# RedFly-Shield_v14.net
KiCad netlist of a schematic drawn in EAGLE
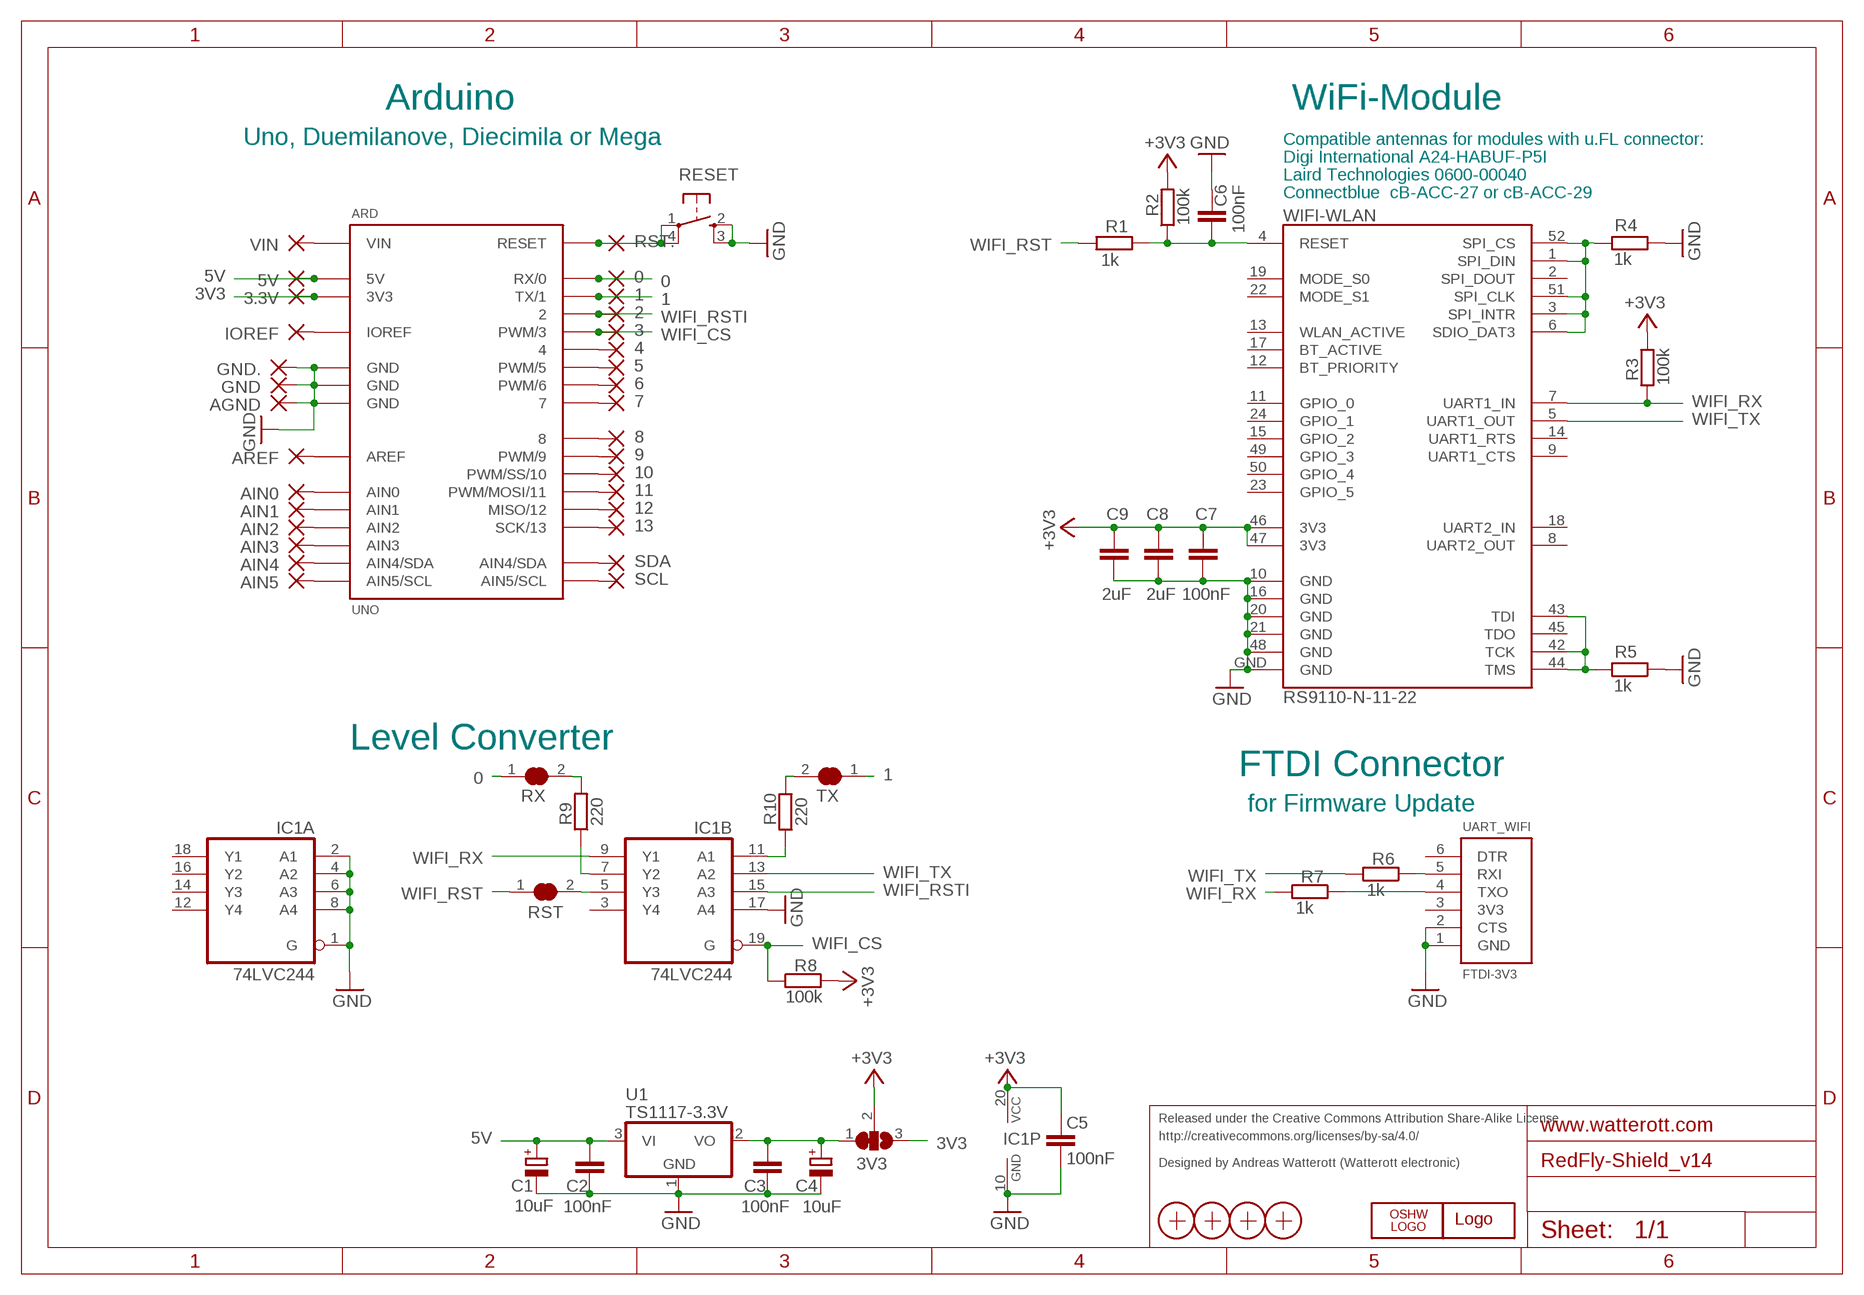
[diagram p0: schematic, sheet 1]

(export (version "E")
  (design (tool "Eeschema 10.0.6"))
  (components
    (comp (ref "0")
      (value "WIREPAD1,6/0,8")
      (footprint "eagle-import:1,6_0,8")
      (libsource (lib "eagle-import") (part "WIREPAD1,6/0,8"))
    )
    (comp (ref "1")
      (value "WIREPAD1,6/0,8")
      (footprint "eagle-import:1,6_0,8")
      (libsource (lib "eagle-import") (part "WIREPAD1,6/0,8"))
    )
    (comp (ref "2")
      (value "WIREPAD1,6/0,8")
      (footprint "eagle-import:1,6_0,8")
      (libsource (lib "eagle-import") (part "WIREPAD1,6/0,8"))
    )
    (comp (ref "3")
      (value "WIREPAD1,6/0,8")
      (footprint "eagle-import:1,6_0,8")
      (libsource (lib "eagle-import") (part "WIREPAD1,6/0,8"))
    )
    (comp (ref "3.3V")
      (value "WIREPAD1,6/0,8")
      (footprint "eagle-import:1,6_0,8")
      (libsource (lib "eagle-import") (part "WIREPAD1,6/0,8"))
    )
    (comp (ref "3V3")
      (value "SJ2W")
      (footprint "eagle-import:SJ_2")
      (libsource (lib "eagle-import") (part "SJ2W"))
    )
    (comp (ref "4")
      (value "WIREPAD1,6/0,8")
      (footprint "eagle-import:1,6_0,8")
      (libsource (lib "eagle-import") (part "WIREPAD1,6/0,8"))
    )
    (comp (ref "5")
      (value "WIREPAD1,6/0,8")
      (footprint "eagle-import:1,6_0,8")
      (libsource (lib "eagle-import") (part "WIREPAD1,6/0,8"))
    )
    (comp (ref "5V")
      (value "WIREPAD1,6/0,8")
      (footprint "eagle-import:1,6_0,8")
      (libsource (lib "eagle-import") (part "WIREPAD1,6/0,8"))
    )
    (comp (ref "6")
      (value "WIREPAD1,6/0,8")
      (footprint "eagle-import:1,6_0,8")
      (libsource (lib "eagle-import") (part "WIREPAD1,6/0,8"))
    )
    (comp (ref "7")
      (value "WIREPAD1,6/0,8")
      (footprint "eagle-import:1,6_0,8")
      (libsource (lib "eagle-import") (part "WIREPAD1,6/0,8"))
    )
    (comp (ref "8")
      (value "WIREPAD1,6/0,8")
      (footprint "eagle-import:1,6_0,8")
      (libsource (lib "eagle-import") (part "WIREPAD1,6/0,8"))
    )
    (comp (ref "9")
      (value "WIREPAD1,6/0,8")
      (footprint "eagle-import:1,6_0,8")
      (libsource (lib "eagle-import") (part "WIREPAD1,6/0,8"))
    )
    (comp (ref "10")
      (value "WIREPAD1,6/0,8")
      (footprint "eagle-import:1,6_0,8")
      (libsource (lib "eagle-import") (part "WIREPAD1,6/0,8"))
    )
    (comp (ref "11")
      (value "WIREPAD1,6/0,8")
      (footprint "eagle-import:1,6_0,8")
      (libsource (lib "eagle-import") (part "WIREPAD1,6/0,8"))
    )
    (comp (ref "12")
      (value "WIREPAD1,6/0,8")
      (footprint "eagle-import:1,6_0,8")
      (libsource (lib "eagle-import") (part "WIREPAD1,6/0,8"))
    )
    (comp (ref "13")
      (value "WIREPAD1,6/0,8")
      (footprint "eagle-import:1,6_0,8")
      (libsource (lib "eagle-import") (part "WIREPAD1,6/0,8"))
    )
    (comp (ref "AGND")
      (value "WIREPAD1,6/0,8")
      (footprint "eagle-import:1,6_0,8")
      (libsource (lib "eagle-import") (part "WIREPAD1,6/0,8"))
    )
    (comp (ref "AIN0")
      (value "WIREPAD1,6/0,8")
      (footprint "eagle-import:1,6_0,8")
      (libsource (lib "eagle-import") (part "WIREPAD1,6/0,8"))
    )
    (comp (ref "AIN1")
      (value "WIREPAD1,6/0,8")
      (footprint "eagle-import:1,6_0,8")
      (libsource (lib "eagle-import") (part "WIREPAD1,6/0,8"))
    )
    (comp (ref "AIN2")
      (value "WIREPAD1,6/0,8")
      (footprint "eagle-import:1,6_0,8")
      (libsource (lib "eagle-import") (part "WIREPAD1,6/0,8"))
    )
    (comp (ref "AIN3")
      (value "WIREPAD1,6/0,8")
      (footprint "eagle-import:1,6_0,8")
      (libsource (lib "eagle-import") (part "WIREPAD1,6/0,8"))
    )
    (comp (ref "AIN4")
      (value "WIREPAD1,6/0,8")
      (footprint "eagle-import:1,6_0,8")
      (libsource (lib "eagle-import") (part "WIREPAD1,6/0,8"))
    )
    (comp (ref "AIN5")
      (value "WIREPAD1,6/0,8")
      (footprint "eagle-import:1,6_0,8")
      (libsource (lib "eagle-import") (part "WIREPAD1,6/0,8"))
    )
    (comp (ref "ARD")
      (value "UNO")
      (footprint "eagle-import:UNO")
      (libsource (lib "eagle-import") (part "UNO"))
    )
    (comp (ref "AREF")
      (value "WIREPAD1,6/0,8")
      (footprint "eagle-import:1,6_0,8")
      (libsource (lib "eagle-import") (part "WIREPAD1,6/0,8"))
    )
    (comp (ref "C1")
      (value "10uF")
      (footprint "eagle-import:153CLV-0505")
      (libsource (lib "eagle-import") (part "CPOL-EU153CLV-0505"))
    )
    (comp (ref "C2")
      (value "100nF")
      (footprint "eagle-import:C0603")
      (libsource (lib "eagle-import") (part "C-EUC0603"))
    )
    (comp (ref "C3")
      (value "100nF")
      (footprint "eagle-import:C0603")
      (libsource (lib "eagle-import") (part "C-EUC0603"))
    )
    (comp (ref "C4")
      (value "10uF")
      (footprint "eagle-import:153CLV-0505")
      (libsource (lib "eagle-import") (part "CPOL-EU153CLV-0505"))
    )
    (comp (ref "C5")
      (value "100nF")
      (footprint "eagle-import:C0603")
      (libsource (lib "eagle-import") (part "C-EUC0603"))
    )
    (comp (ref "C6")
      (value "100nF")
      (footprint "eagle-import:C0603")
      (libsource (lib "eagle-import") (part "C-EUC0603"))
    )
    (comp (ref "C7")
      (value "100nF")
      (footprint "eagle-import:C0603")
      (libsource (lib "eagle-import") (part "C-EUC0603"))
    )
    (comp (ref "C8")
      (value "2uF")
      (footprint "eagle-import:C0603")
      (libsource (lib "eagle-import") (part "C-EUC0603"))
    )
    (comp (ref "C9")
      (value "2uF")
      (footprint "eagle-import:C0603")
      (libsource (lib "eagle-import") (part "C-EUC0603"))
    )
    (comp (ref "GND")
      (value "WIREPAD1,6/0,8")
      (footprint "eagle-import:1,6_0,8")
      (libsource (lib "eagle-import") (part "WIREPAD1,6/0,8"))
    )
    (comp (ref "GND.")
      (value "WIREPAD1,6/0,8")
      (footprint "eagle-import:1,6_0,8")
      (libsource (lib "eagle-import") (part "WIREPAD1,6/0,8"))
    )
    (comp (ref "IC1")
      (value "74LVC244")
      (footprint "eagle-import:SO20W")
      (libsource (lib "eagle-import") (part "74244DWHC"))
    )
    (comp (ref "IOREF")
      (value "WIREPAD1,6/0,8")
      (footprint "eagle-import:1,6_0,8")
      (libsource (lib "eagle-import") (part "WIREPAD1,6/0,8"))
    )
    (comp (ref "LOGO1")
      (value "WE-LOGO")
      (footprint "eagle-import:WE-LOGO")
      (libsource (lib "eagle-import") (part "WE-LOGO"))
    )
    (comp (ref "LOGO2")
      (value "OSHW_LOGO_6MILX0100-NT")
      (footprint "eagle-import:OSHW_6X100_NOTEXT")
      (libsource (lib "eagle-import") (part "OSHW_LOGO_6MILX0100-NT"))
    )
    (comp (ref "R1")
      (value "1k")
      (footprint "eagle-import:R0603")
      (libsource (lib "eagle-import") (part "R-EU_R0603"))
    )
    (comp (ref "R2")
      (value "100k")
      (footprint "eagle-import:R0603")
      (libsource (lib "eagle-import") (part "R-EU_R0603"))
    )
    (comp (ref "R3")
      (value "100k")
      (footprint "eagle-import:R0603")
      (libsource (lib "eagle-import") (part "R-EU_R0603"))
    )
    (comp (ref "R4")
      (value "1k")
      (footprint "eagle-import:R0603")
      (libsource (lib "eagle-import") (part "R-EU_R0603"))
    )
    (comp (ref "R5")
      (value "1k")
      (footprint "eagle-import:R0603")
      (libsource (lib "eagle-import") (part "R-EU_R0603"))
    )
    (comp (ref "R6")
      (value "1k")
      (footprint "eagle-import:R0603")
      (libsource (lib "eagle-import") (part "R-EU_R0603"))
    )
    (comp (ref "R7")
      (value "1k")
      (footprint "eagle-import:R0603")
      (libsource (lib "eagle-import") (part "R-EU_R0603"))
    )
    (comp (ref "R8")
      (value "100k")
      (footprint "eagle-import:R0603")
      (libsource (lib "eagle-import") (part "R-EU_R0603"))
    )
    (comp (ref "R9")
      (value "220")
      (footprint "eagle-import:R0603")
      (libsource (lib "eagle-import") (part "R-EU_R0603"))
    )
    (comp (ref "R10")
      (value "220")
      (footprint "eagle-import:R0603")
      (libsource (lib "eagle-import") (part "R-EU_R0603"))
    )
    (comp (ref "RESET")
      (value "SW_SMDS")
      (footprint "eagle-import:SW_SMD4@1")
      (libsource (lib "eagle-import") (part "SW_SMDS"))
    )
    (comp (ref "RST") (value "SJ") (footprint "eagle-import:SJ") (libsource (lib "eagle-import") (part "SJ")))
    (comp (ref "RST.")
      (value "WIREPAD1,6/0,8")
      (footprint "eagle-import:1,6_0,8")
      (libsource (lib "eagle-import") (part "WIREPAD1,6/0,8"))
    )
    (comp (ref "RX") (value "SJ") (footprint "eagle-import:SJ") (libsource (lib "eagle-import") (part "SJ")))
    (comp (ref "SCL")
      (value "WIREPAD1,6/0,8")
      (footprint "eagle-import:1,6_0,8")
      (libsource (lib "eagle-import") (part "WIREPAD1,6/0,8"))
    )
    (comp (ref "SDA")
      (value "WIREPAD1,6/0,8")
      (footprint "eagle-import:1,6_0,8")
      (libsource (lib "eagle-import") (part "WIREPAD1,6/0,8"))
    )
    (comp (ref "TX") (value "SJ") (footprint "eagle-import:SJ") (libsource (lib "eagle-import") (part "SJ")))
    (comp (ref "U1")
      (value "TS1117-3.3V")
      (footprint "eagle-import:SOT223")
      (libsource (lib "eagle-import") (part "TS1117"))
    )
    (comp (ref "UART_WIFI")
      (value "FTDI-3V3")
      (footprint "eagle-import:FTDI")
      (libsource (lib "eagle-import") (part "FTDI"))
    )
    (comp (ref "VIN")
      (value "WIREPAD1,6/0,8")
      (footprint "eagle-import:1,6_0,8")
      (libsource (lib "eagle-import") (part "WIREPAD1,6/0,8"))
    )
    (comp (ref "WIFI-WLAN")
      (value "RS9110-N-11-22")
      (footprint "eagle-import:RS9110-N-11-21")
      (libsource (lib "eagle-import") (part "RS9110-N-11-21"))
    )
    (comp (ref "X1")
      (value "PASSER")
      (footprint "eagle-import:PASSER")
      (libsource (lib "eagle-import") (part "PASSER"))
    )
    (comp (ref "X2")
      (value "PASSER")
      (footprint "eagle-import:PASSER")
      (libsource (lib "eagle-import") (part "PASSER"))
    )
    (comp (ref "X3")
      (value "PASSER")
      (footprint "eagle-import:PASSER")
      (libsource (lib "eagle-import") (part "PASSER"))
    )
    (comp (ref "X4")
      (value "PASSER")
      (footprint "eagle-import:PASSER")
      (libsource (lib "eagle-import") (part "PASSER"))
    )
  )
  (nets
    (net (code "1") (name "+3V3") (class "Default")
      (node (ref "3V3") (pin "2") (pinfunction "2_2") (pintype "passive"))
      (node (ref "C5") (pin "1") (pinfunction "1_1") (pintype "passive"))
      (node (ref "C7") (pin "1") (pinfunction "1_1") (pintype "passive"))
      (node (ref "C8") (pin "1") (pinfunction "1_1") (pintype "passive"))
      (node (ref "C9") (pin "1") (pinfunction "1_1") (pintype "passive"))
      (node (ref "IC1") (pin "20") (pinfunction "VCC_20") (pintype "power_in"))
      (node (ref "R2") (pin "2") (pinfunction "2_2") (pintype "passive"))
      (node (ref "R3") (pin "1") (pinfunction "1_1") (pintype "passive"))
      (node (ref "R8") (pin "2") (pinfunction "2_2") (pintype "passive"))
      (node (ref "WIFI-WLAN") (pin "46") (pinfunction "3V3_46") (pintype "power_in"))
      (node (ref "WIFI-WLAN") (pin "47") (pinfunction "3V3_47") (pintype "power_in"))
    )
    (net (code "2") (name "/0") (class "Default")
      (node (ref "0") (pin "1") (pinfunction "P_1") (pintype "passive"))
      (node (ref "ARD") (pin "0") (pinfunction "RX/0_0") (pintype "bidirectional"))
      (node (ref "RX") (pin "1") (pinfunction "1_1") (pintype "passive"))
    )
    (net (code "3") (name "/1") (class "Default")
      (node (ref "1") (pin "1") (pinfunction "P_1") (pintype "passive"))
      (node (ref "ARD") (pin "1") (pinfunction "TX/1_1") (pintype "bidirectional"))
      (node (ref "TX") (pin "1") (pinfunction "1_1") (pintype "passive"))
    )
    (net (code "4") (name "/3V3") (class "Default")
      (node (ref "3.3V") (pin "1") (pinfunction "P_1") (pintype "passive"))
      (node (ref "3V3") (pin "3") (pinfunction "3_3") (pintype "passive"))
      (node (ref "ARD") (pin "3V3") (pinfunction "3V3_3V3") (pintype "power_in"))
    )
    (net (code "5") (name "/5V") (class "Default")
      (node (ref "5V") (pin "1") (pinfunction "P_1") (pintype "passive"))
      (node (ref "ARD") (pin "5V") (pinfunction "5V_5V") (pintype "power_in"))
      (node (ref "C1") (pin "+") (pinfunction "+_+") (pintype "passive"))
      (node (ref "C2") (pin "1") (pinfunction "1_1") (pintype "passive"))
      (node (ref "U1") (pin "3") (pinfunction "VI_3") (pintype "input"))
    )
    (net (code "6") (name "/WIFI_CS") (class "Default")
      (node (ref "3") (pin "1") (pinfunction "P_1") (pintype "passive"))
      (node (ref "ARD") (pin "3") (pinfunction "PWM/3_3") (pintype "bidirectional"))
      (node (ref "IC1") (pin "19") (pinfunction "G_19") (pintype "input"))
      (node (ref "R8") (pin "1") (pinfunction "1_1") (pintype "passive"))
    )
    (net (code "7") (name "/WIFI_RST") (class "Default")
      (node (ref "R1") (pin "2") (pinfunction "2_2") (pintype "passive"))
      (node (ref "RST") (pin "1") (pinfunction "1_1") (pintype "passive"))
    )
    (net (code "8") (name "/WIFI_RSTI") (class "Default")
      (node (ref "2") (pin "1") (pinfunction "P_1") (pintype "passive"))
      (node (ref "ARD") (pin "2") (pinfunction "2_2") (pintype "bidirectional"))
      (node (ref "IC1") (pin "15") (pinfunction "A3_15") (pintype "input"))
    )
    (net (code "9") (name "/WIFI_RX") (class "Default")
      (node (ref "IC1") (pin "9") (pinfunction "Y1_9") (pintype "tri_state"))
      (node (ref "R3") (pin "2") (pinfunction "2_2") (pintype "passive"))
      (node (ref "R7") (pin "2") (pinfunction "2_2") (pintype "passive"))
      (node (ref "WIFI-WLAN") (pin "7") (pinfunction "UART1_IN_7") (pintype "bidirectional"))
    )
    (net (code "10") (name "/WIFI_TX") (class "Default")
      (node (ref "IC1") (pin "13") (pinfunction "A2_13") (pintype "input"))
      (node (ref "R6") (pin "2") (pinfunction "2_2") (pintype "passive"))
      (node (ref "WIFI-WLAN") (pin "5") (pinfunction "UART1_OUT_5") (pintype "bidirectional"))
    )
    (net (code "11") (name "GND") (class "Default")
      (node (ref "AGND") (pin "1") (pinfunction "P_1") (pintype "passive"))
      (node (ref "ARD") (pin "GND@1") (pinfunction "GND_GND@1") (pintype "power_in"))
      (node (ref "ARD") (pin "GND@2") (pinfunction "GND_GND@2") (pintype "power_in"))
      (node (ref "ARD") (pin "GND@3") (pinfunction "GND_GND@3") (pintype "power_in"))
      (node (ref "C1") (pin "-") (pinfunction "-_-") (pintype "passive"))
      (node (ref "C2") (pin "2") (pinfunction "2_2") (pintype "passive"))
      (node (ref "C3") (pin "2") (pinfunction "2_2") (pintype "passive"))
      (node (ref "C4") (pin "-") (pinfunction "-_-") (pintype "passive"))
      (node (ref "C5") (pin "2") (pinfunction "2_2") (pintype "passive"))
      (node (ref "C6") (pin "1") (pinfunction "1_1") (pintype "passive"))
      (node (ref "C7") (pin "2") (pinfunction "2_2") (pintype "passive"))
      (node (ref "C8") (pin "2") (pinfunction "2_2") (pintype "passive"))
      (node (ref "C9") (pin "2") (pinfunction "2_2") (pintype "passive"))
      (node (ref "GND") (pin "1") (pinfunction "P_1") (pintype "passive"))
      (node (ref "GND.") (pin "1") (pinfunction "P_1") (pintype "passive"))
      (node (ref "IC1") (pin "1") (pinfunction "G_1") (pintype "input"))
      (node (ref "IC1") (pin "10") (pinfunction "GND_10") (pintype "power_in"))
      (node (ref "IC1") (pin "17") (pinfunction "A4_17") (pintype "input"))
      (node (ref "IC1") (pin "2") (pinfunction "A1_2") (pintype "input"))
      (node (ref "IC1") (pin "4") (pinfunction "A2_4") (pintype "input"))
      (node (ref "IC1") (pin "6") (pinfunction "A3_6") (pintype "input"))
      (node (ref "IC1") (pin "8") (pinfunction "A4_8") (pintype "input"))
      (node (ref "R4") (pin "1") (pinfunction "1_1") (pintype "passive"))
      (node (ref "R5") (pin "1") (pinfunction "1_1") (pintype "passive"))
      (node (ref "RESET") (pin "2") (pinfunction "S_2") (pintype "passive"))
      (node (ref "RESET") (pin "3") (pinfunction "S1_3") (pintype "passive"))
      (node (ref "U1") (pin "1") (pinfunction "GND_1") (pintype "passive"))
      (node (ref "UART_WIFI") (pin "1") (pinfunction "GND_1") (pintype "bidirectional"))
      (node (ref "UART_WIFI") (pin "2") (pinfunction "CTS_2") (pintype "bidirectional"))
      (node (ref "WIFI-WLAN") (pin "10") (pinfunction "GND_10") (pintype "power_in"))
      (node (ref "WIFI-WLAN") (pin "16") (pinfunction "GND_16") (pintype "power_in"))
      (node (ref "WIFI-WLAN") (pin "20") (pinfunction "GND_20") (pintype "power_in"))
      (node (ref "WIFI-WLAN") (pin "21") (pinfunction "GND_21") (pintype "power_in"))
      (node (ref "WIFI-WLAN") (pin "48") (pinfunction "GND_48") (pintype "power_in"))
      (node (ref "WIFI-WLAN") (pin "GND") (pinfunction "GND_GND") (pintype "power_in"))
    )
    (net (code "12") (name "Net-(4-P)") (class "Default")
      (node (ref "4") (pin "1") (pinfunction "P_1") (pintype "passive"))
      (node (ref "ARD") (pin "4") (pinfunction "4_4") (pintype "bidirectional"))
    )
    (net (code "13") (name "Net-(5-P)") (class "Default")
      (node (ref "5") (pin "1") (pinfunction "P_1") (pintype "passive"))
      (node (ref "ARD") (pin "5") (pinfunction "PWM/5_5") (pintype "bidirectional"))
    )
    (net (code "14") (name "Net-(6-P)") (class "Default")
      (node (ref "6") (pin "1") (pinfunction "P_1") (pintype "passive"))
      (node (ref "ARD") (pin "6") (pinfunction "PWM/6_6") (pintype "bidirectional"))
    )
    (net (code "15") (name "Net-(7-P)") (class "Default")
      (node (ref "7") (pin "1") (pinfunction "P_1") (pintype "passive"))
      (node (ref "ARD") (pin "7") (pinfunction "7_7") (pintype "bidirectional"))
    )
    (net (code "16") (name "Net-(8-P)") (class "Default")
      (node (ref "8") (pin "1") (pinfunction "P_1") (pintype "passive"))
      (node (ref "ARD") (pin "8") (pinfunction "8_8") (pintype "bidirectional"))
    )
    (net (code "17") (name "Net-(9-P)") (class "Default")
      (node (ref "9") (pin "1") (pinfunction "P_1") (pintype "passive"))
      (node (ref "ARD") (pin "9") (pinfunction "PWM/9_9") (pintype "bidirectional"))
    )
    (net (code "18") (name "Net-(10-P)") (class "Default")
      (node (ref "10") (pin "1") (pinfunction "P_1") (pintype "passive"))
      (node (ref "ARD") (pin "10") (pinfunction "PWM/SS/10_10") (pintype "bidirectional"))
    )
    (net (code "19") (name "Net-(11-P)") (class "Default")
      (node (ref "11") (pin "1") (pinfunction "P_1") (pintype "passive"))
      (node (ref "ARD") (pin "11") (pinfunction "PWM/MOSI/11_11") (pintype "bidirectional"))
    )
    (net (code "20") (name "Net-(12-P)") (class "Default")
      (node (ref "12") (pin "1") (pinfunction "P_1") (pintype "passive"))
      (node (ref "ARD") (pin "12") (pinfunction "MISO/12_12") (pintype "bidirectional"))
    )
    (net (code "21") (name "Net-(13-P)") (class "Default")
      (node (ref "13") (pin "1") (pinfunction "P_1") (pintype "passive"))
      (node (ref "ARD") (pin "13") (pinfunction "SCK/13_13") (pintype "bidirectional"))
    )
    (net (code "22") (name "Net-(AIN0-P)") (class "Default")
      (node (ref "AIN0") (pin "1") (pinfunction "P_1") (pintype "passive"))
      (node (ref "ARD") (pin "AIN0") (pinfunction "AIN0_AIN0") (pintype "bidirectional"))
    )
    (net (code "23") (name "Net-(AIN1-P)") (class "Default")
      (node (ref "AIN1") (pin "1") (pinfunction "P_1") (pintype "passive"))
      (node (ref "ARD") (pin "AIN1") (pinfunction "AIN1_AIN1") (pintype "bidirectional"))
    )
    (net (code "24") (name "Net-(AIN2-P)") (class "Default")
      (node (ref "AIN2") (pin "1") (pinfunction "P_1") (pintype "passive"))
      (node (ref "ARD") (pin "AIN2") (pinfunction "AIN2_AIN2") (pintype "bidirectional"))
    )
    (net (code "25") (name "Net-(AIN3-P)") (class "Default")
      (node (ref "AIN3") (pin "1") (pinfunction "P_1") (pintype "passive"))
      (node (ref "ARD") (pin "AIN3") (pinfunction "AIN3_AIN3") (pintype "bidirectional"))
    )
    (net (code "26") (name "Net-(AIN4-P)") (class "Default")
      (node (ref "AIN4") (pin "1") (pinfunction "P_1") (pintype "passive"))
      (node (ref "ARD") (pin "AIN4") (pinfunction "AIN4/SDA_AIN4") (pintype "bidirectional"))
    )
    (net (code "27") (name "Net-(AIN5-P)") (class "Default")
      (node (ref "AIN5") (pin "1") (pinfunction "P_1") (pintype "passive"))
      (node (ref "ARD") (pin "AIN5") (pinfunction "AIN5/SCL_AIN5") (pintype "bidirectional"))
    )
    (net (code "28") (name "Net-(ARD-RESET)") (class "Default")
      (node (ref "ARD") (pin "RST") (pinfunction "RESET_RST") (pintype "bidirectional"))
      (node (ref "RESET") (pin "1") (pinfunction "P_1") (pintype "passive"))
      (node (ref "RESET") (pin "4") (pinfunction "P1_4") (pintype "passive"))
      (node (ref "RST.") (pin "1") (pinfunction "P_1") (pintype "passive"))
    )
    (net (code "29") (name "Net-(AREF-P)") (class "Default")
      (node (ref "ARD") (pin "AREF") (pinfunction "AREF_AREF") (pintype "power_in"))
      (node (ref "AREF") (pin "1") (pinfunction "P_1") (pintype "passive"))
    )
    (net (code "30") (name "Net-(IC1B-A1)") (class "Default")
      (node (ref "IC1") (pin "11") (pinfunction "A1_11") (pintype "input"))
      (node (ref "R10") (pin "2") (pinfunction "2_2") (pintype "passive"))
    )
    (net (code "31") (name "Net-(IC1B-Y2)") (class "Default")
      (node (ref "IC1") (pin "7") (pinfunction "Y2_7") (pintype "tri_state"))
      (node (ref "R9") (pin "1") (pinfunction "1_1") (pintype "passive"))
    )
    (net (code "32") (name "Net-(IC1B-Y3)") (class "Default")
      (node (ref "IC1") (pin "5") (pinfunction "Y3_5") (pintype "tri_state"))
      (node (ref "RST") (pin "2") (pinfunction "2_2") (pintype "passive"))
    )
    (net (code "33") (name "Net-(IOREF-P)") (class "Default")
      (node (ref "ARD") (pin "IOREF") (pinfunction "IOREF_IOREF") (pintype "power_in"))
      (node (ref "IOREF") (pin "1") (pinfunction "P_1") (pintype "passive"))
    )
    (net (code "34") (name "Net-(R9-Pad2)") (class "Default")
      (node (ref "R9") (pin "2") (pinfunction "2_2") (pintype "passive"))
      (node (ref "RX") (pin "2") (pinfunction "2_2") (pintype "passive"))
    )
    (net (code "35") (name "Net-(R10-Pad1)") (class "Default")
      (node (ref "R10") (pin "1") (pinfunction "1_1") (pintype "passive"))
      (node (ref "TX") (pin "2") (pinfunction "2_2") (pintype "passive"))
    )
    (net (code "36") (name "Net-(SCL-P)") (class "Default")
      (node (ref "ARD") (pin "SCL") (pinfunction "AIN5/SCL_SCL") (pintype "bidirectional"))
      (node (ref "SCL") (pin "1") (pinfunction "P_1") (pintype "passive"))
    )
    (net (code "37") (name "Net-(SDA-P)") (class "Default")
      (node (ref "ARD") (pin "SDA") (pinfunction "AIN4/SDA_SDA") (pintype "bidirectional"))
      (node (ref "SDA") (pin "1") (pinfunction "P_1") (pintype "passive"))
    )
    (net (code "38") (name "Net-(U1-VO)") (class "Default")
      (node (ref "3V3") (pin "1") (pinfunction "1_1") (pintype "passive"))
      (node (ref "C3") (pin "1") (pinfunction "1_1") (pintype "passive"))
      (node (ref "C4") (pin "+") (pinfunction "+_+") (pintype "passive"))
      (node (ref "U1") (pin "2") (pinfunction "VO_2") (pintype "passive"))
    )
    (net (code "39") (name "Net-(UART_WIFI-RXI)") (class "Default")
      (node (ref "R6") (pin "1") (pinfunction "1_1") (pintype "passive"))
      (node (ref "UART_WIFI") (pin "5") (pinfunction "RXI_5") (pintype "bidirectional"))
    )
    (net (code "40") (name "Net-(UART_WIFI-TXO)") (class "Default")
      (node (ref "R7") (pin "1") (pinfunction "1_1") (pintype "passive"))
      (node (ref "UART_WIFI") (pin "4") (pinfunction "TXO_4") (pintype "bidirectional"))
    )
    (net (code "41") (name "Net-(VIN-P)") (class "Default")
      (node (ref "ARD") (pin "VIN") (pinfunction "VIN_VIN") (pintype "power_in"))
      (node (ref "VIN") (pin "1") (pinfunction "P_1") (pintype "passive"))
    )
    (net (code "42") (name "Net-(WIFI-WLAN-RESET)") (class "Default")
      (node (ref "C6") (pin "2") (pinfunction "2_2") (pintype "passive"))
      (node (ref "R1") (pin "1") (pinfunction "1_1") (pintype "passive"))
      (node (ref "R2") (pin "1") (pinfunction "1_1") (pintype "passive"))
      (node (ref "WIFI-WLAN") (pin "4") (pinfunction "RESET_4") (pintype "bidirectional"))
    )
    (net (code "43") (name "Net-(WIFI-WLAN-SDIO_DAT3)") (class "Default")
      (node (ref "R4") (pin "2") (pinfunction "2_2") (pintype "passive"))
      (node (ref "WIFI-WLAN") (pin "1") (pinfunction "SPI_DIN_1") (pintype "bidirectional"))
      (node (ref "WIFI-WLAN") (pin "3") (pinfunction "SPI_INTR_3") (pintype "bidirectional"))
      (node (ref "WIFI-WLAN") (pin "51") (pinfunction "SPI_CLK_51") (pintype "bidirectional"))
      (node (ref "WIFI-WLAN") (pin "52") (pinfunction "SPI_CS_52") (pintype "bidirectional"))
      (node (ref "WIFI-WLAN") (pin "6") (pinfunction "SDIO_DAT3_6") (pintype "bidirectional"))
    )
    (net (code "44") (name "Net-(WIFI-WLAN-TCK)") (class "Default")
      (node (ref "R5") (pin "2") (pinfunction "2_2") (pintype "passive"))
      (node (ref "WIFI-WLAN") (pin "42") (pinfunction "TCK_42") (pintype "bidirectional"))
      (node (ref "WIFI-WLAN") (pin "43") (pinfunction "TDI_43") (pintype "bidirectional"))
      (node (ref "WIFI-WLAN") (pin "44") (pinfunction "TMS_44") (pintype "bidirectional"))
    )
    (net (code "45") (name "unconnected-(IC1A-Y1-Pad18)") (class "Default")
      (node (ref "IC1") (pin "18") (pinfunction "Y1_18") (pintype "tri_state"))
    )
    (net (code "46") (name "unconnected-(IC1A-Y2-Pad16)") (class "Default")
      (node (ref "IC1") (pin "16") (pinfunction "Y2_16") (pintype "tri_state"))
    )
    (net (code "47") (name "unconnected-(IC1A-Y3-Pad14)") (class "Default")
      (node (ref "IC1") (pin "14") (pinfunction "Y3_14") (pintype "tri_state"))
    )
    (net (code "48") (name "unconnected-(IC1A-Y4-Pad12)") (class "Default")
      (node (ref "IC1") (pin "12") (pinfunction "Y4_12") (pintype "tri_state"))
    )
    (net (code "49") (name "unconnected-(IC1B-Y4-Pad3)") (class "Default")
      (node (ref "IC1") (pin "3") (pinfunction "Y4_3") (pintype "tri_state"))
    )
    (net (code "50") (name "unconnected-(UART_WIFI-3V3-Pad3)") (class "Default")
      (node (ref "UART_WIFI") (pin "3") (pinfunction "3V3_3") (pintype "bidirectional"))
    )
    (net (code "51") (name "unconnected-(UART_WIFI-DTR-Pad6)") (class "Default")
      (node (ref "UART_WIFI") (pin "6") (pinfunction "DTR_6") (pintype "bidirectional"))
    )
    (net (code "52") (name "unconnected-(WIFI-WLAN-BT_ACTIVE-Pad17)") (class "Default")
      (node (ref "WIFI-WLAN") (pin "17") (pinfunction "BT_ACTIVE_17") (pintype "bidirectional"))
    )
    (net (code "53") (name "unconnected-(WIFI-WLAN-BT_PRIORITY-Pad12)") (class "Default")
      (node (ref "WIFI-WLAN") (pin "12") (pinfunction "BT_PRIORITY_12") (pintype "bidirectional"))
    )
    (net (code "54") (name "unconnected-(WIFI-WLAN-GPIO_0-Pad11)") (class "Default")
      (node (ref "WIFI-WLAN") (pin "11") (pinfunction "GPIO_0_11") (pintype "bidirectional"))
    )
    (net (code "55") (name "unconnected-(WIFI-WLAN-GPIO_1-Pad24)") (class "Default")
      (node (ref "WIFI-WLAN") (pin "24") (pinfunction "GPIO_1_24") (pintype "bidirectional"))
    )
    (net (code "56") (name "unconnected-(WIFI-WLAN-GPIO_2-Pad15)") (class "Default")
      (node (ref "WIFI-WLAN") (pin "15") (pinfunction "GPIO_2_15") (pintype "bidirectional"))
    )
    (net (code "57") (name "unconnected-(WIFI-WLAN-GPIO_3-Pad49)") (class "Default")
      (node (ref "WIFI-WLAN") (pin "49") (pinfunction "GPIO_3_49") (pintype "bidirectional"))
    )
    (net (code "58") (name "unconnected-(WIFI-WLAN-GPIO_4-Pad50)") (class "Default")
      (node (ref "WIFI-WLAN") (pin "50") (pinfunction "GPIO_4_50") (pintype "bidirectional"))
    )
    (net (code "59") (name "unconnected-(WIFI-WLAN-GPIO_5-Pad23)") (class "Default")
      (node (ref "WIFI-WLAN") (pin "23") (pinfunction "GPIO_5_23") (pintype "bidirectional"))
    )
    (net (code "60") (name "unconnected-(WIFI-WLAN-MODE_S0-Pad19)") (class "Default")
      (node (ref "WIFI-WLAN") (pin "19") (pinfunction "MODE_S0_19") (pintype "bidirectional"))
    )
    (net (code "61") (name "unconnected-(WIFI-WLAN-MODE_S1-Pad22)") (class "Default")
      (node (ref "WIFI-WLAN") (pin "22") (pinfunction "MODE_S1_22") (pintype "bidirectional"))
    )
    (net (code "62") (name "unconnected-(WIFI-WLAN-SPI_DOUT-Pad2)") (class "Default")
      (node (ref "WIFI-WLAN") (pin "2") (pinfunction "SPI_DOUT_2") (pintype "bidirectional"))
    )
    (net (code "63") (name "unconnected-(WIFI-WLAN-TDO-Pad45)") (class "Default")
      (node (ref "WIFI-WLAN") (pin "45") (pinfunction "TDO_45") (pintype "bidirectional"))
    )
    (net (code "64") (name "unconnected-(WIFI-WLAN-UART1_CTS-Pad9)") (class "Default")
      (node (ref "WIFI-WLAN") (pin "9") (pinfunction "UART1_CTS_9") (pintype "bidirectional"))
    )
    (net (code "65") (name "unconnected-(WIFI-WLAN-UART1_RTS-Pad14)") (class "Default")
      (node (ref "WIFI-WLAN") (pin "14") (pinfunction "UART1_RTS_14") (pintype "bidirectional"))
    )
    (net (code "66") (name "unconnected-(WIFI-WLAN-UART2_IN-Pad18)") (class "Default")
      (node (ref "WIFI-WLAN") (pin "18") (pinfunction "UART2_IN_18") (pintype "bidirectional"))
    )
    (net (code "67") (name "unconnected-(WIFI-WLAN-UART2_OUT-Pad8)") (class "Default")
      (node (ref "WIFI-WLAN") (pin "8") (pinfunction "UART2_OUT_8") (pintype "bidirectional"))
    )
    (net (code "68") (name "unconnected-(WIFI-WLAN-WLAN_ACTIVE-Pad13)") (class "Default")
      (node (ref "WIFI-WLAN") (pin "13") (pinfunction "WLAN_ACTIVE_13") (pintype "bidirectional"))
    )
  )
)
